# lizard-ttl.net
KiCad netlist of a schematic drawn in EAGLE
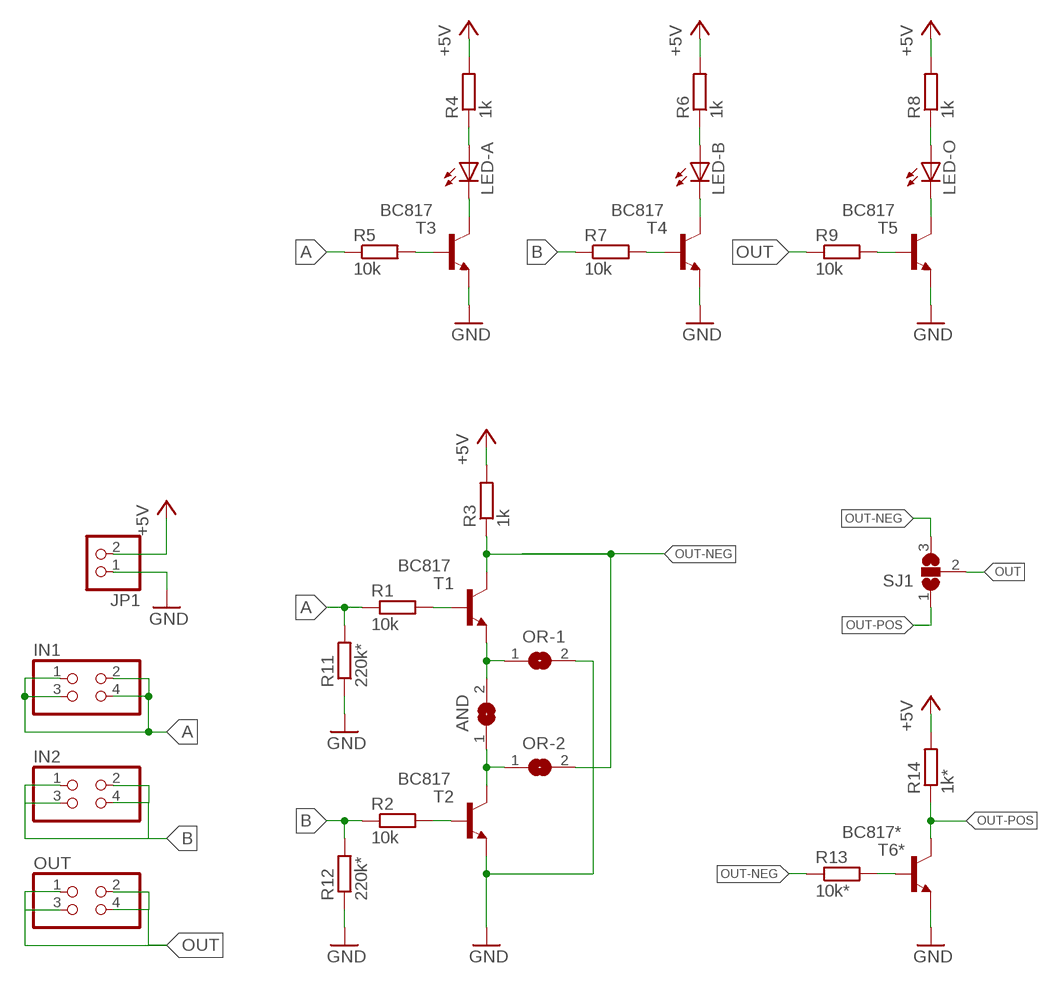
[diagram p0: schematic, sheet 1]

(export (version "E")
  (design (tool "Eeschema 10.0.6"))
  (components
    (comp (ref "AND") (value "SJ") (footprint "eagle-import:SJ") (libsource (lib "eagle-import") (part "SJ")))
    (comp (ref "IN1")
      (value "PINHD-2X2/EDGE")
      (footprint "eagle-import:2X02_EDGE")
      (libsource (lib "eagle-import") (part "PINHD-2X2/EDGE"))
    )
    (comp (ref "IN2")
      (value "PINHD-2X2/EDGE")
      (footprint "eagle-import:2X02_EDGE")
      (libsource (lib "eagle-import") (part "PINHD-2X2/EDGE"))
    )
    (comp (ref "JP1")
      (value "PINHD-1X2")
      (footprint "eagle-import:1X02")
      (libsource (lib "eagle-import") (part "PINHD-1X2"))
    )
    (comp (ref "LED-A")
      (value "LEDCHIPLED_0603")
      (footprint "eagle-import:CHIPLED_0603")
      (libsource (lib "eagle-import") (part "LEDCHIPLED_0603"))
    )
    (comp (ref "LED-B")
      (value "LEDCHIPLED_0603")
      (footprint "eagle-import:CHIPLED_0603")
      (libsource (lib "eagle-import") (part "LEDCHIPLED_0603"))
    )
    (comp (ref "LED-O")
      (value "LEDCHIPLED_0603")
      (footprint "eagle-import:CHIPLED_0603")
      (libsource (lib "eagle-import") (part "LEDCHIPLED_0603"))
    )
    (comp (ref "OR-1")
      (value "SJ")
      (footprint "eagle-import:SJ")
      (libsource (lib "eagle-import") (part "SJ"))
    )
    (comp (ref "OR-2")
      (value "SJ")
      (footprint "eagle-import:SJ")
      (libsource (lib "eagle-import") (part "SJ"))
    )
    (comp (ref "OUT")
      (value "PINHD-2X2/EDGE")
      (footprint "eagle-import:2X02_EDGE")
      (libsource (lib "eagle-import") (part "PINHD-2X2/EDGE"))
    )
    (comp (ref "R1")
      (value "10k")
      (footprint "eagle-import:R0603")
      (libsource (lib "eagle-import") (part "R-EU_R0603"))
    )
    (comp (ref "R2")
      (value "10k")
      (footprint "eagle-import:R0603")
      (libsource (lib "eagle-import") (part "R-EU_R0603"))
    )
    (comp (ref "R3")
      (value "1k")
      (footprint "eagle-import:R0603")
      (libsource (lib "eagle-import") (part "R-EU_R0603"))
    )
    (comp (ref "R4")
      (value "1k")
      (footprint "eagle-import:R0603")
      (libsource (lib "eagle-import") (part "R-EU_R0603"))
    )
    (comp (ref "R5")
      (value "10k")
      (footprint "eagle-import:R0603")
      (libsource (lib "eagle-import") (part "R-EU_R0603"))
    )
    (comp (ref "R6")
      (value "1k")
      (footprint "eagle-import:R0603")
      (libsource (lib "eagle-import") (part "R-EU_R0603"))
    )
    (comp (ref "R7")
      (value "10k")
      (footprint "eagle-import:R0603")
      (libsource (lib "eagle-import") (part "R-EU_R0603"))
    )
    (comp (ref "R8")
      (value "1k")
      (footprint "eagle-import:R0603")
      (libsource (lib "eagle-import") (part "R-EU_R0603"))
    )
    (comp (ref "R9")
      (value "10k")
      (footprint "eagle-import:R0603")
      (libsource (lib "eagle-import") (part "R-EU_R0603"))
    )
    (comp (ref "R11")
      (value "220k*")
      (footprint "eagle-import:R0603")
      (libsource (lib "eagle-import") (part "R-EU_R0603"))
    )
    (comp (ref "R12")
      (value "220k*")
      (footprint "eagle-import:R0603")
      (libsource (lib "eagle-import") (part "R-EU_R0603"))
    )
    (comp (ref "R13")
      (value "10k*")
      (footprint "eagle-import:R0603")
      (libsource (lib "eagle-import") (part "R-EU_R0603"))
    )
    (comp (ref "R14")
      (value "1k*")
      (footprint "eagle-import:R0603")
      (libsource (lib "eagle-import") (part "R-EU_R0603"))
    )
    (comp (ref "SJ1")
      (value "SJ2W")
      (footprint "eagle-import:SJ_2")
      (libsource (lib "eagle-import") (part "SJ2W"))
    )
    (comp (ref "T1")
      (value "BC817")
      (footprint "eagle-import:SOT23-BEC")
      (libsource (lib "eagle-import") (part "-NPN-SOT23-BECBC817-40"))
    )
    (comp (ref "T2")
      (value "BC817")
      (footprint "eagle-import:SOT23-BEC")
      (libsource (lib "eagle-import") (part "-NPN-SOT23-BECBC817-40"))
    )
    (comp (ref "T3")
      (value "BC817")
      (footprint "eagle-import:SOT23-BEC")
      (libsource (lib "eagle-import") (part "-NPN-SOT23-BECBC817-40"))
    )
    (comp (ref "T4")
      (value "BC817")
      (footprint "eagle-import:SOT23-BEC")
      (libsource (lib "eagle-import") (part "-NPN-SOT23-BECBC817-40"))
    )
    (comp (ref "T5")
      (value "BC817")
      (footprint "eagle-import:SOT23-BEC")
      (libsource (lib "eagle-import") (part "-NPN-SOT23-BECBC817-40"))
    )
    (comp (ref "T6*")
      (value "BC817*")
      (footprint "eagle-import:SOT23-BEC")
      (libsource (lib "eagle-import") (part "-NPN-SOT23-BECBC817-40"))
    )
  )
  (nets
    (net (code "1") (name "+5V") (class "Default")
      (node (ref "JP1") (pin "2") (pinfunction "2_2") (pintype "passive"))
      (node (ref "R14") (pin "2") (pinfunction "2_2") (pintype "passive"))
      (node (ref "R3") (pin "2") (pinfunction "2_2") (pintype "passive"))
      (node (ref "R4") (pin "2") (pinfunction "2_2") (pintype "passive"))
      (node (ref "R6") (pin "2") (pinfunction "2_2") (pintype "passive"))
      (node (ref "R8") (pin "2") (pinfunction "2_2") (pintype "passive"))
    )
    (net (code "2") (name "A") (class "Default")
      (node (ref "IN1") (pin "1") (pinfunction "1_1") (pintype "passive"))
      (node (ref "IN1") (pin "2") (pinfunction "2_2") (pintype "passive"))
      (node (ref "IN1") (pin "3") (pinfunction "3_3") (pintype "passive"))
      (node (ref "IN1") (pin "4") (pinfunction "4_4") (pintype "passive"))
      (node (ref "R1") (pin "1") (pinfunction "1_1") (pintype "passive"))
      (node (ref "R11") (pin "2") (pinfunction "2_2") (pintype "passive"))
      (node (ref "R5") (pin "1") (pinfunction "1_1") (pintype "passive"))
    )
    (net (code "3") (name "B") (class "Default")
      (node (ref "IN2") (pin "1") (pinfunction "1_1") (pintype "passive"))
      (node (ref "IN2") (pin "2") (pinfunction "2_2") (pintype "passive"))
      (node (ref "IN2") (pin "3") (pinfunction "3_3") (pintype "passive"))
      (node (ref "IN2") (pin "4") (pinfunction "4_4") (pintype "passive"))
      (node (ref "R12") (pin "2") (pinfunction "2_2") (pintype "passive"))
      (node (ref "R2") (pin "1") (pinfunction "1_1") (pintype "passive"))
      (node (ref "R7") (pin "1") (pinfunction "1_1") (pintype "passive"))
    )
    (net (code "4") (name "GND") (class "Default")
      (node (ref "JP1") (pin "1") (pinfunction "1_1") (pintype "passive"))
      (node (ref "OR-1") (pin "2") (pinfunction "2_2") (pintype "passive"))
      (node (ref "R11") (pin "1") (pinfunction "1_1") (pintype "passive"))
      (node (ref "R12") (pin "1") (pinfunction "1_1") (pintype "passive"))
      (node (ref "T2") (pin "E") (pinfunction "E_E") (pintype "passive"))
      (node (ref "T3") (pin "E") (pinfunction "E_E") (pintype "passive"))
      (node (ref "T4") (pin "E") (pinfunction "E_E") (pintype "passive"))
      (node (ref "T5") (pin "E") (pinfunction "E_E") (pintype "passive"))
      (node (ref "T6*") (pin "E") (pinfunction "E_E") (pintype "passive"))
    )
    (net (code "5") (name "Net-(AND-Pad1)") (class "Default")
      (node (ref "AND") (pin "1") (pinfunction "1_1") (pintype "passive"))
      (node (ref "OR-2") (pin "1") (pinfunction "1_1") (pintype "passive"))
      (node (ref "T2") (pin "C") (pinfunction "C_C") (pintype "passive"))
    )
    (net (code "6") (name "Net-(AND-Pad2)") (class "Default")
      (node (ref "AND") (pin "2") (pinfunction "2_2") (pintype "passive"))
      (node (ref "OR-1") (pin "1") (pinfunction "1_1") (pintype "passive"))
      (node (ref "T1") (pin "E") (pinfunction "E_E") (pintype "passive"))
    )
    (net (code "7") (name "Net-(LED-A-PadA)") (class "Default")
      (node (ref "LED-A") (pin "A") (pinfunction "A_A") (pintype "passive"))
      (node (ref "R4") (pin "1") (pinfunction "1_1") (pintype "passive"))
    )
    (net (code "8") (name "Net-(LED-A-PadC)") (class "Default")
      (node (ref "LED-A") (pin "C") (pinfunction "C_C") (pintype "passive"))
      (node (ref "T3") (pin "C") (pinfunction "C_C") (pintype "passive"))
    )
    (net (code "9") (name "Net-(LED-B-PadA)") (class "Default")
      (node (ref "LED-B") (pin "A") (pinfunction "A_A") (pintype "passive"))
      (node (ref "R6") (pin "1") (pinfunction "1_1") (pintype "passive"))
    )
    (net (code "10") (name "Net-(LED-B-PadC)") (class "Default")
      (node (ref "LED-B") (pin "C") (pinfunction "C_C") (pintype "passive"))
      (node (ref "T4") (pin "C") (pinfunction "C_C") (pintype "passive"))
    )
    (net (code "11") (name "Net-(LED-O-PadA)") (class "Default")
      (node (ref "LED-O") (pin "A") (pinfunction "A_A") (pintype "passive"))
      (node (ref "R8") (pin "1") (pinfunction "1_1") (pintype "passive"))
    )
    (net (code "12") (name "Net-(LED-O-PadC)") (class "Default")
      (node (ref "LED-O") (pin "C") (pinfunction "C_C") (pintype "passive"))
      (node (ref "T5") (pin "C") (pinfunction "C_C") (pintype "passive"))
    )
    (net (code "13") (name "Net-(R1-Pad2)") (class "Default")
      (node (ref "R1") (pin "2") (pinfunction "2_2") (pintype "passive"))
      (node (ref "T1") (pin "B") (pinfunction "B_B") (pintype "passive"))
    )
    (net (code "14") (name "Net-(R2-Pad2)") (class "Default")
      (node (ref "R2") (pin "2") (pinfunction "2_2") (pintype "passive"))
      (node (ref "T2") (pin "B") (pinfunction "B_B") (pintype "passive"))
    )
    (net (code "15") (name "Net-(R5-Pad2)") (class "Default")
      (node (ref "R5") (pin "2") (pinfunction "2_2") (pintype "passive"))
      (node (ref "T3") (pin "B") (pinfunction "B_B") (pintype "passive"))
    )
    (net (code "16") (name "Net-(R7-Pad2)") (class "Default")
      (node (ref "R7") (pin "2") (pinfunction "2_2") (pintype "passive"))
      (node (ref "T4") (pin "B") (pinfunction "B_B") (pintype "passive"))
    )
    (net (code "17") (name "Net-(R9-Pad2)") (class "Default")
      (node (ref "R9") (pin "2") (pinfunction "2_2") (pintype "passive"))
      (node (ref "T5") (pin "B") (pinfunction "B_B") (pintype "passive"))
    )
    (net (code "18") (name "Net-(R13-Pad2)") (class "Default")
      (node (ref "R13") (pin "2") (pinfunction "2_2") (pintype "passive"))
      (node (ref "T6*") (pin "B") (pinfunction "B_B") (pintype "passive"))
    )
    (net (code "19") (name "OUT") (class "Default")
      (node (ref "OUT") (pin "1") (pinfunction "1_1") (pintype "passive"))
      (node (ref "OUT") (pin "2") (pinfunction "2_2") (pintype "passive"))
      (node (ref "OUT") (pin "3") (pinfunction "3_3") (pintype "passive"))
      (node (ref "OUT") (pin "4") (pinfunction "4_4") (pintype "passive"))
      (node (ref "R9") (pin "1") (pinfunction "1_1") (pintype "passive"))
      (node (ref "SJ1") (pin "2") (pinfunction "2_2") (pintype "passive"))
    )
    (net (code "20") (name "OUT-NEG") (class "Default")
      (node (ref "OR-2") (pin "2") (pinfunction "2_2") (pintype "passive"))
      (node (ref "R13") (pin "1") (pinfunction "1_1") (pintype "passive"))
      (node (ref "R3") (pin "1") (pinfunction "1_1") (pintype "passive"))
      (node (ref "SJ1") (pin "3") (pinfunction "3_3") (pintype "passive"))
      (node (ref "T1") (pin "C") (pinfunction "C_C") (pintype "passive"))
    )
    (net (code "21") (name "OUT-POS") (class "Default")
      (node (ref "R14") (pin "1") (pinfunction "1_1") (pintype "passive"))
      (node (ref "SJ1") (pin "1") (pinfunction "1_1") (pintype "passive"))
      (node (ref "T6*") (pin "C") (pinfunction "C_C") (pintype "passive"))
    )
  )
)
